# LM2576_V1_0.net
KiCad netlist of a schematic drawn in Altium Designer
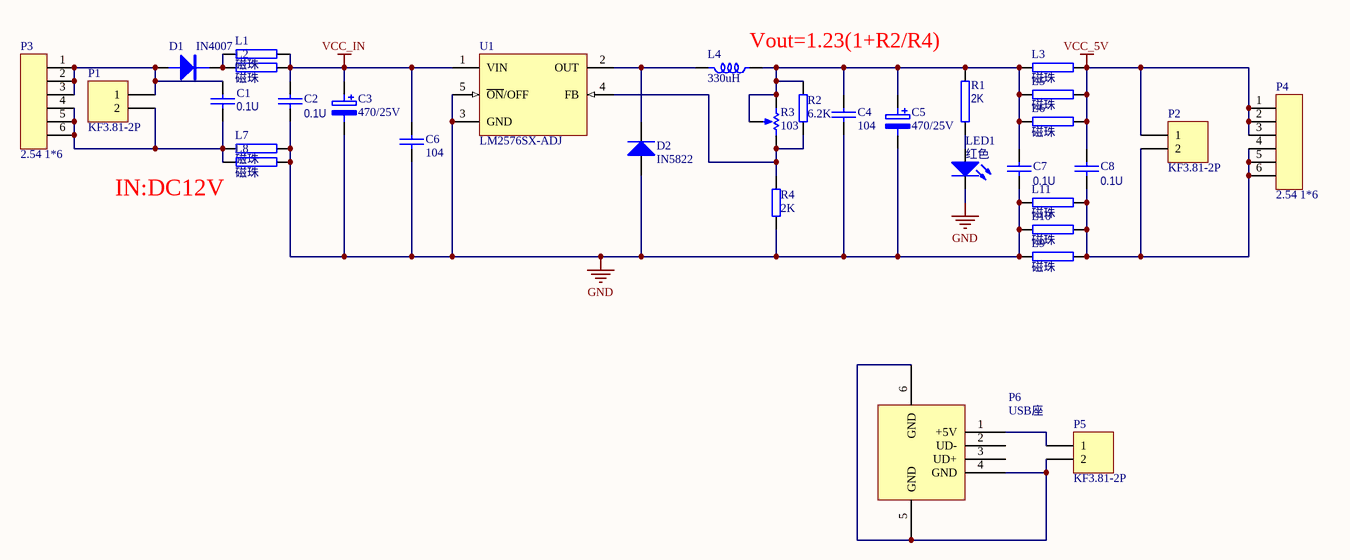
[diagram p0: LM2576_V1.0.schdoc]

(export (version "E")
  (design (tool "Eeschema 10.0.6"))
  (components
    (comp (ref "C1") (value "0.1U") (footprint "0805") (libsource (lib "*") (part "CAP")))
    (comp (ref "C2") (value "0.1U") (footprint "0805") (libsource (lib "*") (part "CAP")))
    (comp (ref "C3")
      (value "470/25V")
      (footprint "电容 铝电解 470U/35V")
      (libsource (lib "Sch_Device_veryaz") (part "电容 贴片 铝电解 470u/25V"))
    )
    (comp (ref "C4")
      (value "104")
      (footprint "0805")
      (libsource (lib "Sch_Device_veryaz") (part "电容 贴片 0805"))
    )
    (comp (ref "C5")
      (value "470/25V")
      (footprint "电容 铝电解 470U/35V")
      (libsource (lib "Sch_Device_veryaz") (part "电容 贴片 铝电解 470u/25V"))
    )
    (comp (ref "C6")
      (value "104")
      (footprint "0805")
      (libsource (lib "Sch_Device_veryaz") (part "电容 贴片 0805"))
    )
    (comp (ref "C7") (value "0.1U") (footprint "0805") (libsource (lib "*") (part "CAP")))
    (comp (ref "C8") (value "0.1U") (footprint "0805") (libsource (lib "*") (part "CAP")))
    (comp (ref "D1") (value "IN4007") (footprint "二极管 贴片 4007") (libsource (lib "*") (part "DIODE")))
    (comp (ref "D2")
      (value "IN5822")
      (footprint "二极管 贴片 4007")
      (libsource (lib "Sch_Device_veryaz") (part "二极管 贴片4007"))
    )
    (comp (ref "L1") (value "磁珠") (footprint "0805") (libsource (lib "*") (part "RES2")))
    (comp (ref "L2") (value "磁珠") (footprint "0805") (libsource (lib "*") (part "RES2")))
    (comp (ref "L3") (value "磁珠") (footprint "0805") (libsource (lib "*") (part "RES2")))
    (comp (ref "L4")
      (value "330uH")
      (footprint "电感 贴片 12*12")
      (libsource (lib "Sch_Device_veryaz") (part "电感 贴片 0805"))
    )
    (comp (ref "L5") (value "磁珠") (footprint "0805") (libsource (lib "*") (part "RES2")))
    (comp (ref "L6") (value "磁珠") (footprint "0805") (libsource (lib "*") (part "RES2")))
    (comp (ref "L7") (value "磁珠") (footprint "0805") (libsource (lib "*") (part "RES2")))
    (comp (ref "L8") (value "磁珠") (footprint "0805") (libsource (lib "*") (part "RES2")))
    (comp (ref "L9") (value "磁珠") (footprint "0805") (libsource (lib "*") (part "RES2")))
    (comp (ref "L10") (value "磁珠") (footprint "0805") (libsource (lib "*") (part "RES2")))
    (comp (ref "L11") (value "磁珠") (footprint "0805") (libsource (lib "*") (part "RES2")))
    (comp (ref "LED1")
      (value "红色")
      (footprint "LED0805")
      (libsource (lib "Sch_Device_veryaz") (part "二极管 贴片发光 0805"))
    )
    (comp (ref "P1")
      (value "KF3.81-2P")
      (footprint "KF127S-3.81-2P")
      (libsource (lib "Sch_Device_veryaz") (part "联结件 XH2.54-2"))
    )
    (comp (ref "P2")
      (value "KF3.81-2P")
      (footprint "KF127S-3.81-2P")
      (libsource (lib "") (part "联结件 XH2.54-2_1"))
    )
    (comp (ref "P3")
      (value "2.54 1*6")
      (footprint "单排插针 2.54 1*6")
      (libsource (lib "Sch_Device_veryaz") (part "连接件 单排插针 2.54 1*6"))
    )
    (comp (ref "P4")
      (value "2.54 1*6")
      (footprint "单排插针 2.54 1*6")
      (libsource (lib "") (part "连接件 单排插针 2.54 1*6_1"))
    )
    (comp (ref "P5")
      (value "KF3.81-2P")
      (footprint "KF127S-3.81-2P")
      (libsource (lib "") (part "联结件 XH2.54-2_1"))
    )
    (comp (ref "P6")
      (value "USB座")
      (footprint "USB座 母头1 侧卧")
      (libsource (lib "Sch_Device_veryaz") (part "连接件 USB座"))
    )
    (comp (ref "R1") (value "2K") (footprint "0805") (libsource (lib "*") (part "RES2")))
    (comp (ref "R2")
      (value "6.2K")
      (footprint "0805")
      (libsource (lib "Sch_Device_veryaz") (part "电阻 贴片 0805"))
    )
    (comp (ref "R3") (value "103") (footprint "电位器") (libsource (lib "基本原器件") (part "电位器 3296")))
    (comp (ref "R4")
      (value "2K")
      (footprint "0805")
      (libsource (lib "Sch_Device_veryaz") (part "电阻 贴片 0805"))
    )
    (comp (ref "U1")
      (value "LM2576SX-ADJ")
      (footprint "TO263 LM2576")
      (description "DC-DC芯片")
      (libsource (lib "Miscellaneous Devices LC") (part "LM2576SX-5.0"))
    )
  )
  (nets
    (net (code "1") (name "GND") (class "Default")
      (node (ref "C2") (pin "1") (pintype "passive"))
      (node (ref "C3") (pin "2") (pintype "passive"))
      (node (ref "C4") (pin "1") (pintype "passive"))
      (node (ref "C5") (pin "2") (pintype "passive"))
      (node (ref "C6") (pin "1") (pintype "passive"))
      (node (ref "C7") (pin "1") (pintype "passive"))
      (node (ref "D2") (pin "1") (pinfunction "A_1") (pintype "passive"))
      (node (ref "L10") (pin "1") (pintype "passive"))
      (node (ref "L11") (pin "1") (pintype "passive"))
      (node (ref "L7") (pin "1") (pintype "passive"))
      (node (ref "L8") (pin "1") (pintype "passive"))
      (node (ref "L9") (pin "1") (pintype "passive"))
      (node (ref "LED1") (pin "2") (pinfunction "K_2") (pintype "passive"))
      (node (ref "R4") (pin "2") (pinfunction "2_2") (pintype "passive"))
      (node (ref "U1") (pin "3") (pinfunction "GND_3") (pintype "power_in"))
      (node (ref "U1") (pin "5") (pinfunction "~{ON}/OFF_5") (pintype "input"))
    )
    (net (code "2") (name "Net-(C1-Pad1)") (class "Default")
      (node (ref "C1") (pin "1") (pintype "passive"))
      (node (ref "L7") (pin "2") (pintype "passive"))
      (node (ref "L8") (pin "2") (pintype "passive"))
      (node (ref "P1") (pin "2") (pinfunction "2_2") (pintype "passive"))
      (node (ref "P3") (pin "4") (pinfunction "4_4") (pintype "passive"))
      (node (ref "P3") (pin "5") (pinfunction "5_5") (pintype "passive"))
      (node (ref "P3") (pin "6") (pinfunction "6_6") (pintype "passive"))
    )
    (net (code "3") (name "Net-(C1-Pad2)") (class "Default")
      (node (ref "C1") (pin "2") (pintype "passive"))
      (node (ref "D1") (pin "1") (pintype "passive"))
      (node (ref "P1") (pin "1") (pinfunction "1_1") (pintype "passive"))
      (node (ref "P3") (pin "1") (pinfunction "1_1") (pintype "passive"))
      (node (ref "P3") (pin "2") (pinfunction "2_2") (pintype "passive"))
      (node (ref "P3") (pin "3") (pinfunction "3_3") (pintype "passive"))
    )
    (net (code "4") (name "Net-(C8-Pad1)") (class "Default")
      (node (ref "C8") (pin "1") (pintype "passive"))
      (node (ref "L10") (pin "2") (pintype "passive"))
      (node (ref "L11") (pin "2") (pintype "passive"))
      (node (ref "L9") (pin "2") (pintype "passive"))
      (node (ref "P2") (pin "2") (pinfunction "2_2") (pintype "passive"))
      (node (ref "P4") (pin "4") (pinfunction "4_4") (pintype "passive"))
      (node (ref "P4") (pin "5") (pinfunction "5_5") (pintype "passive"))
      (node (ref "P4") (pin "6") (pinfunction "6_6") (pintype "passive"))
    )
    (net (code "5") (name "Net-(D1-Pad2)") (class "Default")
      (node (ref "D1") (pin "2") (pintype "passive"))
      (node (ref "L1") (pin "2") (pintype "passive"))
      (node (ref "L2") (pin "2") (pintype "passive"))
    )
    (net (code "6") (name "Net-(D2-K)") (class "Default")
      (node (ref "D2") (pin "2") (pinfunction "K_2") (pintype "passive"))
      (node (ref "L4") (pin "1") (pinfunction "1_1") (pintype "passive"))
      (node (ref "U1") (pin "2") (pinfunction "OUT_2") (pintype "power_in"))
    )
    (net (code "7") (name "Net-(LED1-A)") (class "Default")
      (node (ref "LED1") (pin "1") (pinfunction "A_1") (pintype "passive"))
      (node (ref "R1") (pin "1") (pintype "passive"))
    )
    (net (code "8") (name "Net-(P5-Pad2)") (class "Default")
      (node (ref "P5") (pin "2") (pinfunction "2_2") (pintype "passive"))
      (node (ref "P6") (pin "4") (pinfunction "GND_4") (pintype "passive"))
      (node (ref "P6") (pin "5") (pinfunction "GND_5") (pintype "passive"))
      (node (ref "P6") (pin "6") (pinfunction "GND_6") (pintype "passive"))
    )
    (net (code "9") (name "Net-(P6-+5V)") (class "Default")
      (node (ref "P5") (pin "1") (pinfunction "1_1") (pintype "passive"))
      (node (ref "P6") (pin "1") (pinfunction "+5V_1") (pintype "passive"))
    )
    (net (code "10") (name "Net-(R3-BOT)") (class "Default")
      (node (ref "R2") (pin "2") (pinfunction "2_2") (pintype "passive"))
      (node (ref "R3") (pin "3") (pinfunction "BOT_3") (pintype "passive"))
      (node (ref "R4") (pin "1") (pinfunction "1_1") (pintype "passive"))
      (node (ref "U1") (pin "4") (pinfunction "FB_4") (pintype "input"))
    )
    (net (code "11") (name "Net-(R3-TAP)") (class "Default")
      (node (ref "C4") (pin "2") (pintype "passive"))
      (node (ref "C5") (pin "1") (pintype "passive"))
      (node (ref "C7") (pin "2") (pintype "passive"))
      (node (ref "L3") (pin "1") (pintype "passive"))
      (node (ref "L4") (pin "2") (pinfunction "2_2") (pintype "passive"))
      (node (ref "L5") (pin "1") (pintype "passive"))
      (node (ref "L6") (pin "1") (pintype "passive"))
      (node (ref "R1") (pin "2") (pintype "passive"))
      (node (ref "R2") (pin "1") (pinfunction "1_1") (pintype "passive"))
      (node (ref "R3") (pin "1") (pinfunction "TOP_1") (pintype "passive"))
      (node (ref "R3") (pin "2") (pinfunction "TAP_2") (pintype "passive"))
    )
    (net (code "12") (name "VCC_5V") (class "Default")
      (node (ref "C8") (pin "2") (pintype "passive"))
      (node (ref "L3") (pin "2") (pintype "passive"))
      (node (ref "L5") (pin "2") (pintype "passive"))
      (node (ref "L6") (pin "2") (pintype "passive"))
      (node (ref "P2") (pin "1") (pinfunction "1_1") (pintype "passive"))
      (node (ref "P4") (pin "1") (pinfunction "1_1") (pintype "passive"))
      (node (ref "P4") (pin "2") (pinfunction "2_2") (pintype "passive"))
      (node (ref "P4") (pin "3") (pinfunction "3_3") (pintype "passive"))
    )
    (net (code "13") (name "VCC_IN") (class "Default")
      (node (ref "C2") (pin "2") (pintype "passive"))
      (node (ref "C3") (pin "1") (pintype "passive"))
      (node (ref "C6") (pin "2") (pintype "passive"))
      (node (ref "L1") (pin "1") (pintype "passive"))
      (node (ref "L2") (pin "1") (pintype "passive"))
      (node (ref "U1") (pin "1") (pinfunction "VIN_1") (pintype "power_in"))
    )
    (net (code "14") (name "unconnected-(P6-UD+-Pad3)") (class "Default")
      (node (ref "P6") (pin "3") (pinfunction "UD+_3") (pintype "passive"))
    )
    (net (code "15") (name "unconnected-(P6-UD--Pad2)") (class "Default")
      (node (ref "P6") (pin "2") (pinfunction "UD-_2") (pintype "passive"))
    )
  )
)
